# agitator.net
KiCad netlist of a schematic drawn in EAGLE
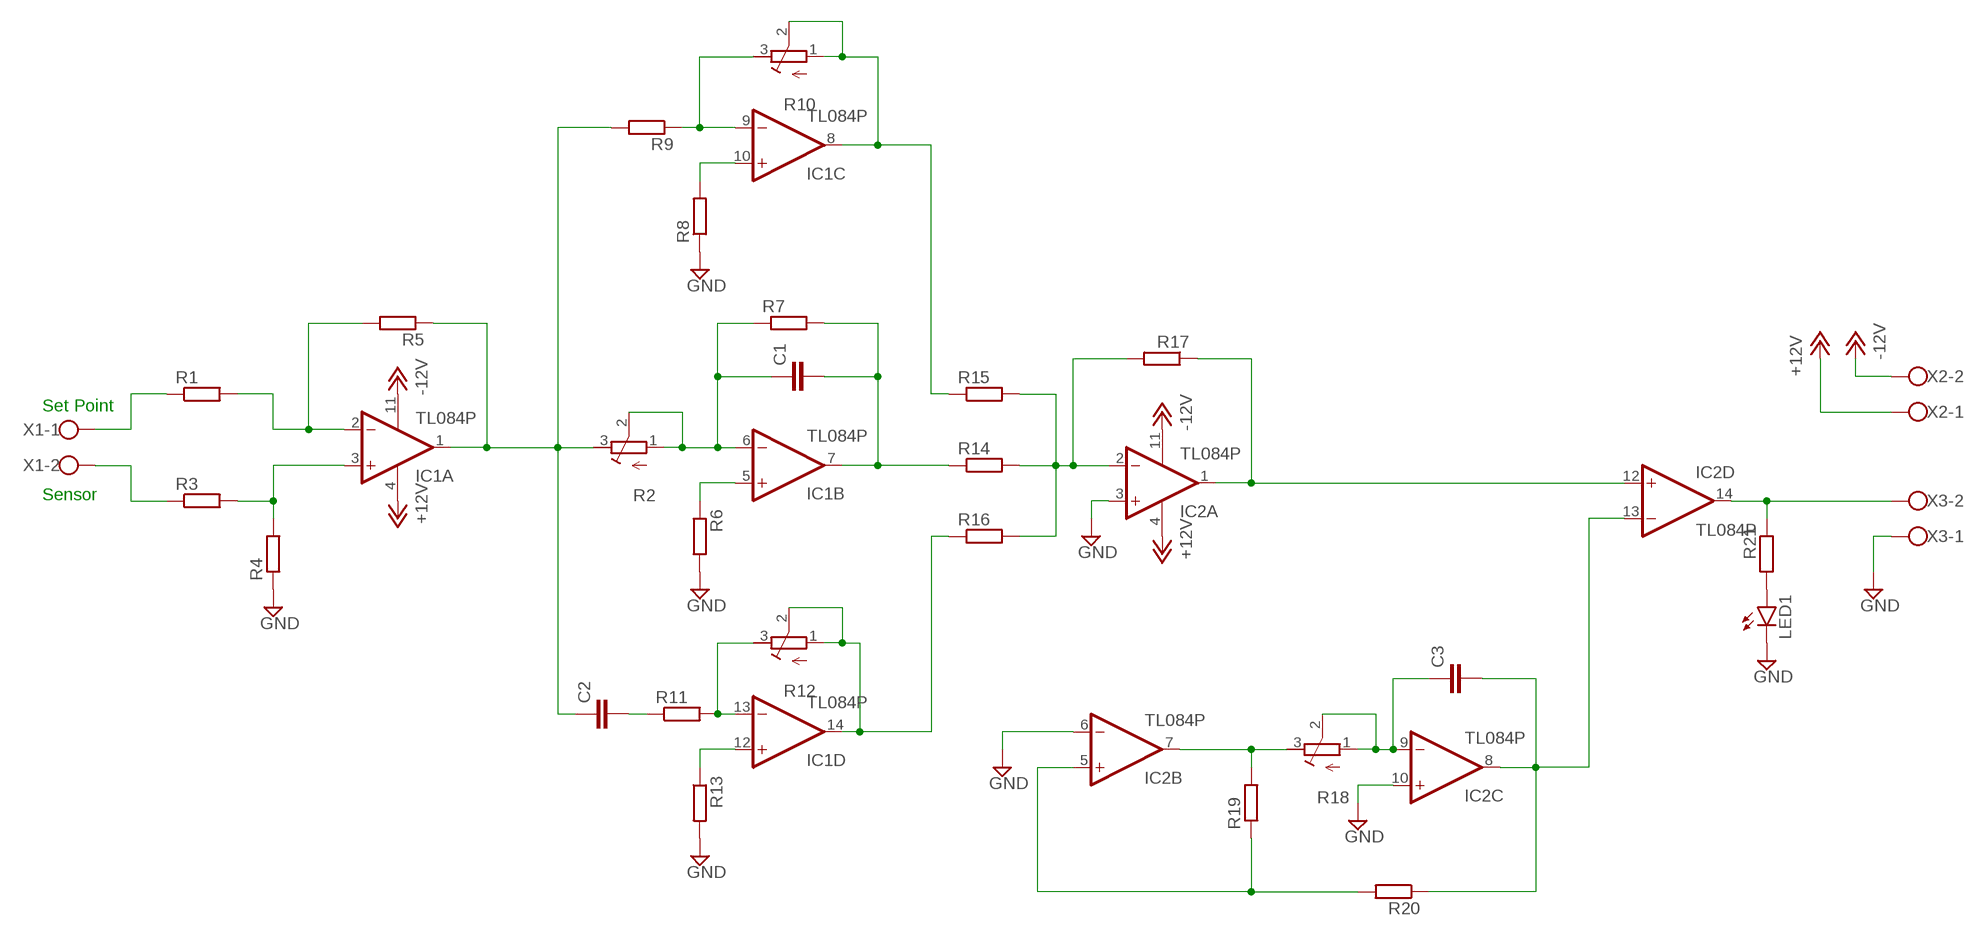
[diagram p0: schematic, sheet 1]

(export (version "E")
  (design (tool "Eeschema 10.0.6"))
  (components
    (comp (ref "C1")
      (value "C2.5/2")
      (footprint "eagle-import:C2.5-2")
      (libsource (lib "eagle-import") (part "C2.5/2"))
    )
    (comp (ref "C2")
      (value "C2.5/2")
      (footprint "eagle-import:C2.5-2")
      (libsource (lib "eagle-import") (part "C2.5/2"))
    )
    (comp (ref "C3")
      (value "C2.5/2")
      (footprint "eagle-import:C2.5-2")
      (libsource (lib "eagle-import") (part "C2.5/2"))
    )
    (comp (ref "IC1")
      (value "TL084P")
      (footprint "eagle-import:DIL14")
      (libsource (lib "eagle-import") (part "TL084P"))
    )
    (comp (ref "IC2")
      (value "TL084P")
      (footprint "eagle-import:DIL14")
      (libsource (lib "eagle-import") (part "TL084P"))
    )
    (comp (ref "LED1")
      (value "LED3MM")
      (footprint "eagle-import:LED3MM")
      (libsource (lib "eagle-import") (part "LED3MM"))
    )
    (comp (ref "R1")
      (value "R-EU_0207/10")
      (footprint "eagle-import:0207_10")
      (libsource (lib "eagle-import") (part "R-EU_0207/10"))
    )
    (comp (ref "R2")
      (value "R-TRIMM64W")
      (footprint "eagle-import:RTRIM64W")
      (libsource (lib "eagle-import") (part "R-TRIMM64W"))
    )
    (comp (ref "R3")
      (value "R-EU_0207/10")
      (footprint "eagle-import:0207_10")
      (libsource (lib "eagle-import") (part "R-EU_0207/10"))
    )
    (comp (ref "R4")
      (value "R-EU_0207/10")
      (footprint "eagle-import:0207_10")
      (libsource (lib "eagle-import") (part "R-EU_0207/10"))
    )
    (comp (ref "R5")
      (value "R-EU_0207/10")
      (footprint "eagle-import:0207_10")
      (libsource (lib "eagle-import") (part "R-EU_0207/10"))
    )
    (comp (ref "R6")
      (value "R-EU_0207/10")
      (footprint "eagle-import:0207_10")
      (libsource (lib "eagle-import") (part "R-EU_0207/10"))
    )
    (comp (ref "R7")
      (value "R-EU_0207/10")
      (footprint "eagle-import:0207_10")
      (libsource (lib "eagle-import") (part "R-EU_0207/10"))
    )
    (comp (ref "R8")
      (value "R-EU_0207/10")
      (footprint "eagle-import:0207_10")
      (libsource (lib "eagle-import") (part "R-EU_0207/10"))
    )
    (comp (ref "R9")
      (value "R-EU_0207/10")
      (footprint "eagle-import:0207_10")
      (libsource (lib "eagle-import") (part "R-EU_0207/10"))
    )
    (comp (ref "R10")
      (value "R-TRIMM64W")
      (footprint "eagle-import:RTRIM64W")
      (libsource (lib "eagle-import") (part "R-TRIMM64W"))
    )
    (comp (ref "R11")
      (value "R-EU_0207/10")
      (footprint "eagle-import:0207_10")
      (libsource (lib "eagle-import") (part "R-EU_0207/10"))
    )
    (comp (ref "R12")
      (value "R-TRIMM64W")
      (footprint "eagle-import:RTRIM64W")
      (libsource (lib "eagle-import") (part "R-TRIMM64W"))
    )
    (comp (ref "R13")
      (value "R-EU_0207/10")
      (footprint "eagle-import:0207_10")
      (libsource (lib "eagle-import") (part "R-EU_0207/10"))
    )
    (comp (ref "R14")
      (value "R-EU_0207/10")
      (footprint "eagle-import:0207_10")
      (libsource (lib "eagle-import") (part "R-EU_0207/10"))
    )
    (comp (ref "R15")
      (value "R-EU_0207/10")
      (footprint "eagle-import:0207_10")
      (libsource (lib "eagle-import") (part "R-EU_0207/10"))
    )
    (comp (ref "R16")
      (value "R-EU_0207/10")
      (footprint "eagle-import:0207_10")
      (libsource (lib "eagle-import") (part "R-EU_0207/10"))
    )
    (comp (ref "R17")
      (value "R-EU_0207/10")
      (footprint "eagle-import:0207_10")
      (libsource (lib "eagle-import") (part "R-EU_0207/10"))
    )
    (comp (ref "R18")
      (value "R-TRIMM64W")
      (footprint "eagle-import:RTRIM64W")
      (libsource (lib "eagle-import") (part "R-TRIMM64W"))
    )
    (comp (ref "R19")
      (value "R-EU_0207/10")
      (footprint "eagle-import:0207_10")
      (libsource (lib "eagle-import") (part "R-EU_0207/10"))
    )
    (comp (ref "R20")
      (value "R-EU_0207/10")
      (footprint "eagle-import:0207_10")
      (libsource (lib "eagle-import") (part "R-EU_0207/10"))
    )
    (comp (ref "R21")
      (value "R-EU_0207/10")
      (footprint "eagle-import:0207_10")
      (libsource (lib "eagle-import") (part "R-EU_0207/10"))
    )
    (comp (ref "X1")
      (value "W237-102")
      (footprint "eagle-import:W237-102")
      (fields (field (name "MPN") "237-102"))
      (libsource (lib "eagle-import") (part "W237-102"))
    )
    (comp (ref "X2")
      (value "W237-102")
      (footprint "eagle-import:W237-102")
      (fields (field (name "MPN") "237-102"))
      (libsource (lib "eagle-import") (part "W237-102"))
    )
    (comp (ref "X3")
      (value "W237-102")
      (footprint "eagle-import:W237-102")
      (fields (field (name "MPN") "237-102"))
      (libsource (lib "eagle-import") (part "W237-102"))
    )
  )
  (nets
    (net (code "1") (name "+12V") (class "Default")
      (node (ref "IC1") (pin "4") (pinfunction "V+_4") (pintype "power_in"))
      (node (ref "IC2") (pin "4") (pinfunction "V+_4") (pintype "power_in"))
      (node (ref "X2") (pin "1") (pinfunction "KL_1") (pintype "passive"))
    )
    (net (code "2") (name "-12V") (class "Default")
      (node (ref "IC1") (pin "11") (pinfunction "V-_11") (pintype "power_in"))
      (node (ref "IC2") (pin "11") (pinfunction "V-_11") (pintype "power_in"))
      (node (ref "X2") (pin "2") (pinfunction "KL_2") (pintype "passive"))
    )
    (net (code "3") (name "GND") (class "Default")
      (node (ref "IC2") (pin "10") (pinfunction "+IN_10") (pintype "input"))
      (node (ref "IC2") (pin "3") (pinfunction "+IN_3") (pintype "input"))
      (node (ref "IC2") (pin "6") (pinfunction "-IN_6") (pintype "input"))
      (node (ref "LED1") (pin "K") (pinfunction "C_K") (pintype "passive"))
      (node (ref "R13") (pin "2") (pinfunction "2_2") (pintype "passive"))
      (node (ref "R4") (pin "1") (pinfunction "1_1") (pintype "passive"))
      (node (ref "R6") (pin "2") (pinfunction "2_2") (pintype "passive"))
      (node (ref "R8") (pin "1") (pinfunction "1_1") (pintype "passive"))
      (node (ref "X3") (pin "1") (pinfunction "KL_1") (pintype "passive"))
    )
    (net (code "4") (name "Net-(C2-Pad2)") (class "Default")
      (node (ref "C2") (pin "2") (pinfunction "2_2") (pintype "passive"))
      (node (ref "R11") (pin "1") (pinfunction "1_1") (pintype "passive"))
    )
    (net (code "5") (name "Net-(IC1A-+IN)") (class "Default")
      (node (ref "IC1") (pin "3") (pinfunction "+IN_3") (pintype "input"))
      (node (ref "R3") (pin "2") (pinfunction "2_2") (pintype "passive"))
      (node (ref "R4") (pin "2") (pinfunction "2_2") (pintype "passive"))
    )
    (net (code "6") (name "Net-(IC1A--IN)") (class "Default")
      (node (ref "IC1") (pin "2") (pinfunction "-IN_2") (pintype "input"))
      (node (ref "R1") (pin "2") (pinfunction "2_2") (pintype "passive"))
      (node (ref "R5") (pin "2") (pinfunction "2_2") (pintype "passive"))
    )
    (net (code "7") (name "Net-(IC1A-OUT)") (class "Default")
      (node (ref "C2") (pin "1") (pinfunction "1_1") (pintype "passive"))
      (node (ref "IC1") (pin "1") (pinfunction "OUT_1") (pintype "output"))
      (node (ref "R2") (pin "3") (pinfunction "E_3") (pintype "passive"))
      (node (ref "R5") (pin "1") (pinfunction "1_1") (pintype "passive"))
      (node (ref "R9") (pin "2") (pinfunction "2_2") (pintype "passive"))
    )
    (net (code "8") (name "Net-(IC1B-+IN)") (class "Default")
      (node (ref "IC1") (pin "5") (pinfunction "+IN_5") (pintype "input"))
      (node (ref "R6") (pin "1") (pinfunction "1_1") (pintype "passive"))
    )
    (net (code "9") (name "Net-(IC1B--IN)") (class "Default")
      (node (ref "C1") (pin "1") (pinfunction "1_1") (pintype "passive"))
      (node (ref "IC1") (pin "6") (pinfunction "-IN_6") (pintype "input"))
      (node (ref "R2") (pin "1") (pinfunction "A_1") (pintype "passive"))
      (node (ref "R2") (pin "2") (pinfunction "S_2") (pintype "passive"))
      (node (ref "R7") (pin "1") (pinfunction "1_1") (pintype "passive"))
    )
    (net (code "10") (name "Net-(IC1B-OUT)") (class "Default")
      (node (ref "C1") (pin "2") (pinfunction "2_2") (pintype "passive"))
      (node (ref "IC1") (pin "7") (pinfunction "OUT_7") (pintype "output"))
      (node (ref "R14") (pin "1") (pinfunction "1_1") (pintype "passive"))
      (node (ref "R7") (pin "2") (pinfunction "2_2") (pintype "passive"))
    )
    (net (code "11") (name "Net-(IC1C-+IN)") (class "Default")
      (node (ref "IC1") (pin "10") (pinfunction "+IN_10") (pintype "input"))
      (node (ref "R8") (pin "2") (pinfunction "2_2") (pintype "passive"))
    )
    (net (code "12") (name "Net-(IC1C--IN)") (class "Default")
      (node (ref "IC1") (pin "9") (pinfunction "-IN_9") (pintype "input"))
      (node (ref "R10") (pin "3") (pinfunction "E_3") (pintype "passive"))
      (node (ref "R9") (pin "1") (pinfunction "1_1") (pintype "passive"))
    )
    (net (code "13") (name "Net-(IC1C-OUT)") (class "Default")
      (node (ref "IC1") (pin "8") (pinfunction "OUT_8") (pintype "output"))
      (node (ref "R10") (pin "1") (pinfunction "A_1") (pintype "passive"))
      (node (ref "R10") (pin "2") (pinfunction "S_2") (pintype "passive"))
      (node (ref "R15") (pin "1") (pinfunction "1_1") (pintype "passive"))
    )
    (net (code "14") (name "Net-(IC1D-+IN)") (class "Default")
      (node (ref "IC1") (pin "12") (pinfunction "+IN_12") (pintype "input"))
      (node (ref "R13") (pin "1") (pinfunction "1_1") (pintype "passive"))
    )
    (net (code "15") (name "Net-(IC1D--IN)") (class "Default")
      (node (ref "IC1") (pin "13") (pinfunction "-IN_13") (pintype "input"))
      (node (ref "R11") (pin "2") (pinfunction "2_2") (pintype "passive"))
      (node (ref "R12") (pin "3") (pinfunction "E_3") (pintype "passive"))
    )
    (net (code "16") (name "Net-(IC1D-OUT)") (class "Default")
      (node (ref "IC1") (pin "14") (pinfunction "OUT_14") (pintype "output"))
      (node (ref "R12") (pin "1") (pinfunction "A_1") (pintype "passive"))
      (node (ref "R12") (pin "2") (pinfunction "S_2") (pintype "passive"))
      (node (ref "R16") (pin "1") (pinfunction "1_1") (pintype "passive"))
    )
    (net (code "17") (name "Net-(IC2A--IN)") (class "Default")
      (node (ref "IC2") (pin "2") (pinfunction "-IN_2") (pintype "input"))
      (node (ref "R14") (pin "2") (pinfunction "2_2") (pintype "passive"))
      (node (ref "R15") (pin "2") (pinfunction "2_2") (pintype "passive"))
      (node (ref "R16") (pin "2") (pinfunction "2_2") (pintype "passive"))
      (node (ref "R17") (pin "2") (pinfunction "2_2") (pintype "passive"))
    )
    (net (code "18") (name "Net-(IC2A-OUT)") (class "Default")
      (node (ref "IC2") (pin "1") (pinfunction "OUT_1") (pintype "output"))
      (node (ref "IC2") (pin "12") (pinfunction "+IN_12") (pintype "input"))
      (node (ref "R17") (pin "1") (pinfunction "1_1") (pintype "passive"))
    )
    (net (code "19") (name "Net-(IC2B-+IN)") (class "Default")
      (node (ref "IC2") (pin "5") (pinfunction "+IN_5") (pintype "input"))
      (node (ref "R19") (pin "1") (pinfunction "1_1") (pintype "passive"))
      (node (ref "R20") (pin "2") (pinfunction "2_2") (pintype "passive"))
    )
    (net (code "20") (name "Net-(IC2B-OUT)") (class "Default")
      (node (ref "IC2") (pin "7") (pinfunction "OUT_7") (pintype "output"))
      (node (ref "R18") (pin "3") (pinfunction "E_3") (pintype "passive"))
      (node (ref "R19") (pin "2") (pinfunction "2_2") (pintype "passive"))
    )
    (net (code "21") (name "Net-(IC2C--IN)") (class "Default")
      (node (ref "C3") (pin "1") (pinfunction "1_1") (pintype "passive"))
      (node (ref "IC2") (pin "9") (pinfunction "-IN_9") (pintype "input"))
      (node (ref "R18") (pin "1") (pinfunction "A_1") (pintype "passive"))
      (node (ref "R18") (pin "2") (pinfunction "S_2") (pintype "passive"))
    )
    (net (code "22") (name "Net-(IC2C-OUT)") (class "Default")
      (node (ref "C3") (pin "2") (pinfunction "2_2") (pintype "passive"))
      (node (ref "IC2") (pin "13") (pinfunction "-IN_13") (pintype "input"))
      (node (ref "IC2") (pin "8") (pinfunction "OUT_8") (pintype "output"))
      (node (ref "R20") (pin "1") (pinfunction "1_1") (pintype "passive"))
    )
    (net (code "23") (name "Net-(IC2D-OUT)") (class "Default")
      (node (ref "IC2") (pin "14") (pinfunction "OUT_14") (pintype "output"))
      (node (ref "R21") (pin "1") (pinfunction "1_1") (pintype "passive"))
      (node (ref "X3") (pin "2") (pinfunction "KL_2") (pintype "passive"))
    )
    (net (code "24") (name "Net-(LED1-PadA)") (class "Default")
      (node (ref "LED1") (pin "A") (pinfunction "A_A") (pintype "passive"))
      (node (ref "R21") (pin "2") (pinfunction "2_2") (pintype "passive"))
    )
    (net (code "25") (name "Net-(X1A-KL)") (class "Default")
      (node (ref "R1") (pin "1") (pinfunction "1_1") (pintype "passive"))
      (node (ref "X1") (pin "1") (pinfunction "KL_1") (pintype "passive"))
    )
    (net (code "26") (name "Net-(X1B-KL)") (class "Default")
      (node (ref "R3") (pin "1") (pinfunction "1_1") (pintype "passive"))
      (node (ref "X1") (pin "2") (pinfunction "KL_2") (pintype "passive"))
    )
  )
)
